# Sheet1.net
KiCad netlist of a schematic drawn in Altium Designer
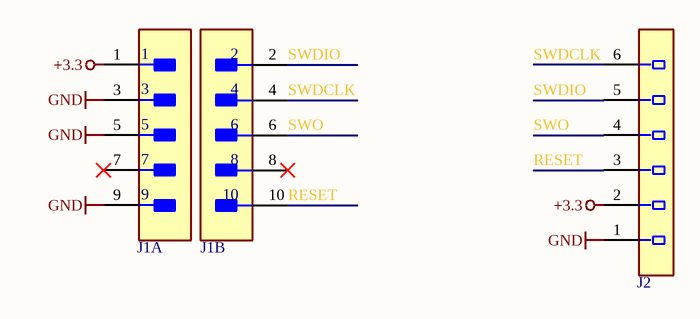
[diagram p0: Sheet1.SchDoc]

(export (version "E")
  (design (tool "Eeschema 10.0.6"))
  (components
    (comp (ref "J1")
      (value "Connector 10 pin")
      (footprint "Amphenol_ICC_-_FCI_0_MFG")
      (fields (field (name "PART NUMBER") "20021121-00010C4LF"))
      (libsource (lib "E-component") (part "Connector 10 pin"))
    )
    (comp (ref "J2")
      (value "Connector")
      (footprint "DS1013-6")
      (libsource (lib "E-component") (part "Connector 6 pin"))
    )
  )
  (nets
    (net (code "1") (name "+3.3") (class "Default")
      (node (ref "J1") (pin "1") (pinfunction "1_1") (pintype "passive"))
      (node (ref "J2") (pin "2") (pinfunction "2_2") (pintype "passive"))
    )
    (net (code "2") (name "/RESET") (class "Default")
      (node (ref "J1") (pin "10") (pinfunction "10_10") (pintype "passive"))
      (node (ref "J2") (pin "3") (pinfunction "3_3") (pintype "passive"))
    )
    (net (code "3") (name "/SWDCLK") (class "Default")
      (node (ref "J1") (pin "4") (pinfunction "4_4") (pintype "passive"))
      (node (ref "J2") (pin "6") (pinfunction "6_6") (pintype "passive"))
    )
    (net (code "4") (name "/SWDIO") (class "Default")
      (node (ref "J1") (pin "2") (pinfunction "2_2") (pintype "passive"))
      (node (ref "J2") (pin "5") (pinfunction "5_5") (pintype "passive"))
    )
    (net (code "5") (name "/SWO") (class "Default")
      (node (ref "J1") (pin "6") (pinfunction "6_6") (pintype "passive"))
      (node (ref "J2") (pin "4") (pinfunction "4_4") (pintype "passive"))
    )
    (net (code "6") (name "GND") (class "Default")
      (node (ref "J1") (pin "3") (pinfunction "3_3") (pintype "passive"))
      (node (ref "J1") (pin "5") (pinfunction "5_5") (pintype "passive"))
      (node (ref "J1") (pin "9") (pinfunction "9_9") (pintype "passive"))
      (node (ref "J2") (pin "1") (pinfunction "1_1") (pintype "passive"))
    )
    (net (code "7") (name "unconnected-(J1-Pad7)") (class "Default")
      (node (ref "J1") (pin "7") (pinfunction "7_7") (pintype "passive+no_connect"))
    )
    (net (code "8") (name "unconnected-(J1-Pad8)") (class "Default")
      (node (ref "J1") (pin "8") (pinfunction "8_8") (pintype "passive+no_connect"))
    )
  )
)
